# shield.net
KiCad netlist of a schematic drawn in EAGLE
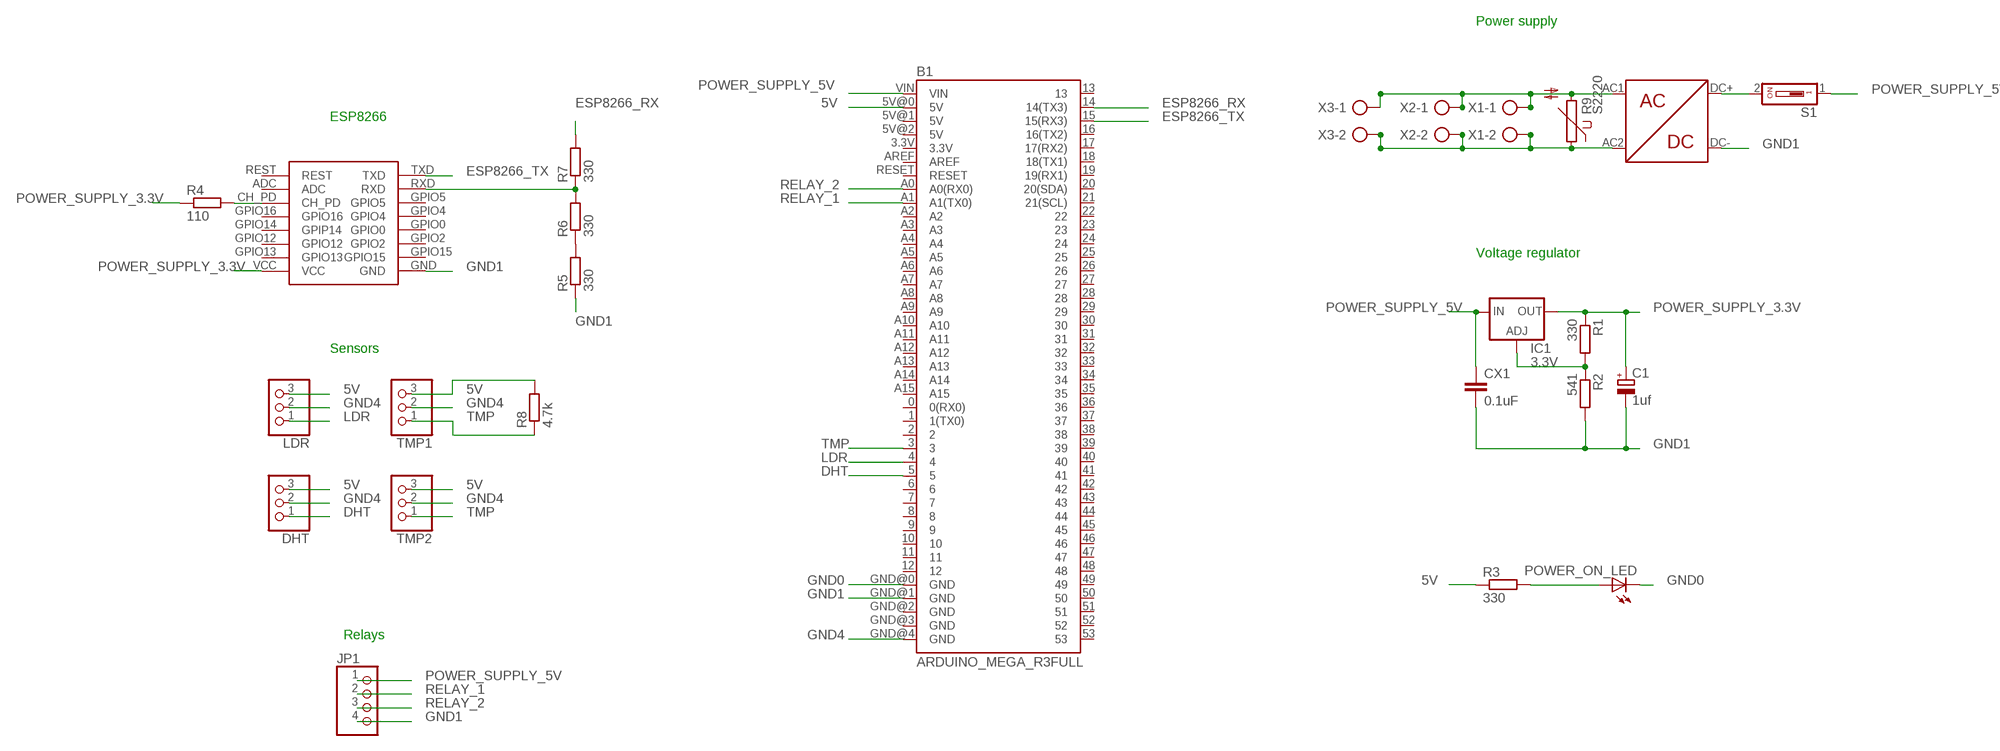
[diagram p0: schematic, sheet 1]

(export (version "E")
  (design (tool "Eeschema 10.0.6"))
  (components
    (comp (ref "B1")
      (value "ARDUINO_MEGA_R3FULL")
      (footprint "eagle-import:ARDUINO_MEGA")
      (libsource (lib "eagle-import") (part "ARDUINO_MEGA_R3FULL"))
    )
    (comp (ref "C1")
      (value "1uf")
      (footprint "eagle-import:TT2D5")
      (libsource (lib "eagle-import") (part "CPOL-EUTT2D5"))
    )
    (comp (ref "CX1")
      (value "0.1uF")
      (footprint "eagle-import:XC10B5")
      (libsource (lib "eagle-import") (part "CXXC10B5"))
    )
    (comp (ref "DHT")
      (value "PINHD-1X3")
      (footprint "eagle-import:1X03")
      (libsource (lib "eagle-import") (part "PINHD-1X3"))
    )
    (comp (ref "IC1")
      (value "3.3V")
      (footprint "eagle-import:317TL")
      (libsource (lib "eagle-import") (part "LM317TL"))
    )
    (comp (ref "JP1")
      (value "PINHD-1X4")
      (footprint "eagle-import:1X04")
      (libsource (lib "eagle-import") (part "PINHD-1X4"))
    )
    (comp (ref "LDR")
      (value "PINHD-1X3")
      (footprint "eagle-import:1X03")
      (libsource (lib "eagle-import") (part "PINHD-1X3"))
    )
    (comp (ref "POWER_ON_LED")
      (value "LED5MM")
      (footprint "eagle-import:LED5MM")
      (libsource (lib "eagle-import") (part "LED5MM"))
    )
    (comp (ref "R1")
      (value "330")
      (footprint "eagle-import:0204_7")
      (libsource (lib "eagle-import") (part "R0204/7"))
    )
    (comp (ref "R2")
      (value "541")
      (footprint "eagle-import:0204_7")
      (libsource (lib "eagle-import") (part "R0204/7"))
    )
    (comp (ref "R3")
      (value "330")
      (footprint "eagle-import:0204_7")
      (libsource (lib "eagle-import") (part "R0204/7"))
    )
    (comp (ref "R4")
      (value "110")
      (footprint "eagle-import:0204_7")
      (libsource (lib "eagle-import") (part "R0204/7"))
    )
    (comp (ref "R5")
      (value "330")
      (footprint "eagle-import:0204_7")
      (libsource (lib "eagle-import") (part "R0204/7"))
    )
    (comp (ref "R6")
      (value "330")
      (footprint "eagle-import:0204_7")
      (libsource (lib "eagle-import") (part "R0204/7"))
    )
    (comp (ref "R7")
      (value "330")
      (footprint "eagle-import:0204_7")
      (libsource (lib "eagle-import") (part "R0204/7"))
    )
    (comp (ref "R8")
      (value "4.7k")
      (footprint "eagle-import:0204_7")
      (libsource (lib "eagle-import") (part "R0204/7"))
    )
    (comp (ref "R9")
      (value "S2220")
      (footprint "eagle-import:S2220")
      (libsource (lib "eagle-import") (part "S2220"))
    )
    (comp (ref "S1")
      (value "SD4-01")
      (footprint "eagle-import:SD4-01")
      (libsource (lib "eagle-import") (part "SD4-01"))
    )
    (comp (ref "TMP1")
      (value "PINHD-1X3")
      (footprint "eagle-import:1X03")
      (libsource (lib "eagle-import") (part "PINHD-1X3"))
    )
    (comp (ref "TMP2")
      (value "PINHD-1X3")
      (footprint "eagle-import:1X03")
      (libsource (lib "eagle-import") (part "PINHD-1X3"))
    )
    (comp (ref "U$1")
      (value "HLK-PM01")
      (footprint "eagle-import:HLK-PM01")
      (libsource (lib "eagle-import") (part "HLK-PM01"))
    )
    (comp (ref "U$4")
      (value "ESP8266_SHIELD")
      (footprint "eagle-import:ESP8266_SHIELD")
      (libsource (lib "eagle-import") (part "ESP8266_SHIELD"))
    )
    (comp (ref "X1")
      (value "AK500/2-H")
      (footprint "eagle-import:AK500_2-H")
      (libsource (lib "eagle-import") (part "AK500/2-H"))
    )
    (comp (ref "X2")
      (value "AK500/2-H")
      (footprint "eagle-import:AK500_2-H")
      (libsource (lib "eagle-import") (part "AK500/2-H"))
    )
    (comp (ref "X3")
      (value "AK500/2-H")
      (footprint "eagle-import:AK500_2-H")
      (libsource (lib "eagle-import") (part "AK500/2-H"))
    )
  )
  (nets
    (net (code "1") (name "/5V") (class "Default")
      (node (ref "B1") (pin "5V@0") (pinfunction "5V_5V@0") (pintype "bidirectional"))
      (node (ref "DHT") (pin "3") (pinfunction "3_3") (pintype "passive"))
      (node (ref "LDR") (pin "3") (pinfunction "3_3") (pintype "passive"))
      (node (ref "R3") (pin "1") (pinfunction "1_1") (pintype "passive"))
      (node (ref "R8") (pin "2") (pinfunction "2_2") (pintype "passive"))
      (node (ref "TMP1") (pin "3") (pinfunction "3_3") (pintype "passive"))
      (node (ref "TMP2") (pin "3") (pinfunction "3_3") (pintype "passive"))
    )
    (net (code "2") (name "/DHT") (class "Default")
      (node (ref "B1") (pin "5") (pinfunction "5_5") (pintype "bidirectional"))
      (node (ref "DHT") (pin "1") (pinfunction "1_1") (pintype "passive"))
    )
    (net (code "3") (name "/ESP8266_RX") (class "Default")
      (node (ref "B1") (pin "14") (pinfunction "14(TX3)_14") (pintype "bidirectional"))
      (node (ref "R7") (pin "2") (pinfunction "2_2") (pintype "passive"))
    )
    (net (code "4") (name "/ESP8266_TX") (class "Default")
      (node (ref "B1") (pin "15") (pinfunction "15(RX3)_15") (pintype "bidirectional"))
      (node (ref "U$4") (pin "TXD") (pinfunction "TXD_TXD") (pintype "bidirectional"))
    )
    (net (code "5") (name "/GND0") (class "Default")
      (node (ref "B1") (pin "GND@0") (pinfunction "GND_GND@0") (pintype "bidirectional"))
      (node (ref "POWER_ON_LED") (pin "K") (pinfunction "C_K") (pintype "passive"))
    )
    (net (code "6") (name "/GND1") (class "Default")
      (node (ref "B1") (pin "GND@1") (pinfunction "GND_GND@1") (pintype "bidirectional"))
      (node (ref "C1") (pin "-") (pinfunction "-_-") (pintype "passive"))
      (node (ref "CX1") (pin "2") (pinfunction "2_2") (pintype "passive"))
      (node (ref "JP1") (pin "4") (pinfunction "4_4") (pintype "passive"))
      (node (ref "R2") (pin "2") (pinfunction "2_2") (pintype "passive"))
      (node (ref "R5") (pin "1") (pinfunction "1_1") (pintype "passive"))
      (node (ref "U$1") (pin "DC-") (pinfunction "DC-_DC-") (pintype "power_in"))
      (node (ref "U$4") (pin "GND") (pinfunction "GND_GND") (pintype "bidirectional"))
    )
    (net (code "7") (name "/GND4") (class "Default")
      (node (ref "B1") (pin "GND@4") (pinfunction "GND_GND@4") (pintype "bidirectional"))
      (node (ref "DHT") (pin "2") (pinfunction "2_2") (pintype "passive"))
      (node (ref "LDR") (pin "2") (pinfunction "2_2") (pintype "passive"))
      (node (ref "TMP1") (pin "2") (pinfunction "2_2") (pintype "passive"))
      (node (ref "TMP2") (pin "2") (pinfunction "2_2") (pintype "passive"))
    )
    (net (code "8") (name "/LDR") (class "Default")
      (node (ref "B1") (pin "4") (pinfunction "4_4") (pintype "bidirectional"))
      (node (ref "LDR") (pin "1") (pinfunction "1_1") (pintype "passive"))
    )
    (net (code "9") (name "/POWER_SUPPLY_3.3V") (class "Default")
      (node (ref "C1") (pin "+") (pinfunction "+_+") (pintype "passive"))
      (node (ref "IC1") (pin "2") (pinfunction "OUT_2") (pintype "passive"))
      (node (ref "R1") (pin "1") (pinfunction "1_1") (pintype "passive"))
      (node (ref "R4") (pin "1") (pinfunction "1_1") (pintype "passive"))
      (node (ref "U$4") (pin "VCC") (pinfunction "VCC_VCC") (pintype "bidirectional"))
    )
    (net (code "10") (name "/POWER_SUPPLY_5V") (class "Default")
      (node (ref "B1") (pin "VIN") (pinfunction "VIN_VIN") (pintype "bidirectional"))
      (node (ref "CX1") (pin "1") (pinfunction "1_1") (pintype "passive"))
      (node (ref "IC1") (pin "3") (pinfunction "IN_3") (pintype "input"))
      (node (ref "JP1") (pin "1") (pinfunction "1_1") (pintype "passive"))
      (node (ref "S1") (pin "1") (pinfunction "1_1") (pintype "passive"))
    )
    (net (code "11") (name "/RELAY_1") (class "Default")
      (node (ref "B1") (pin "A1") (pinfunction "A1(TX0)_A1") (pintype "bidirectional"))
      (node (ref "JP1") (pin "2") (pinfunction "2_2") (pintype "passive"))
    )
    (net (code "12") (name "/RELAY_2") (class "Default")
      (node (ref "B1") (pin "A0") (pinfunction "A0(RX0)_A0") (pintype "bidirectional"))
      (node (ref "JP1") (pin "3") (pinfunction "3_3") (pintype "passive"))
    )
    (net (code "13") (name "/TMP") (class "Default")
      (node (ref "B1") (pin "3") (pinfunction "3_3") (pintype "bidirectional"))
      (node (ref "R8") (pin "1") (pinfunction "1_1") (pintype "passive"))
      (node (ref "TMP1") (pin "1") (pinfunction "1_1") (pintype "passive"))
      (node (ref "TMP2") (pin "1") (pinfunction "1_1") (pintype "passive"))
    )
    (net (code "14") (name "Net-(IC1-ADJ)") (class "Default")
      (node (ref "IC1") (pin "1") (pinfunction "ADJ_1") (pintype "input"))
      (node (ref "R1") (pin "2") (pinfunction "2_2") (pintype "passive"))
      (node (ref "R2") (pin "1") (pinfunction "1_1") (pintype "passive"))
    )
    (net (code "15") (name "Net-(POWER_ON_LED-PadA)") (class "Default")
      (node (ref "POWER_ON_LED") (pin "A") (pinfunction "A_A") (pintype "passive"))
      (node (ref "R3") (pin "2") (pinfunction "2_2") (pintype "passive"))
    )
    (net (code "16") (name "Net-(R4-Pad2)") (class "Default")
      (node (ref "R4") (pin "2") (pinfunction "2_2") (pintype "passive"))
      (node (ref "U$4") (pin "CH_PD") (pinfunction "CH_PD_CH_PD") (pintype "bidirectional"))
    )
    (net (code "17") (name "Net-(R5-Pad2)") (class "Default")
      (node (ref "R5") (pin "2") (pinfunction "2_2") (pintype "passive"))
      (node (ref "R6") (pin "1") (pinfunction "1_1") (pintype "passive"))
    )
    (net (code "18") (name "Net-(R6-Pad2)") (class "Default")
      (node (ref "R6") (pin "2") (pinfunction "2_2") (pintype "passive"))
      (node (ref "R7") (pin "1") (pinfunction "1_1") (pintype "passive"))
      (node (ref "U$4") (pin "RXD") (pinfunction "RXD_RXD") (pintype "bidirectional"))
    )
    (net (code "19") (name "Net-(S1-Pad2)") (class "Default")
      (node (ref "S1") (pin "2") (pinfunction "2_2") (pintype "passive"))
      (node (ref "U$1") (pin "DC+") (pinfunction "DC+_DC+") (pintype "power_in"))
    )
    (net (code "20") (name "Net-(X1A-KL)") (class "Default")
      (node (ref "R9") (pin "2") (pinfunction "2_2") (pintype "passive"))
      (node (ref "U$1") (pin "AC1") (pinfunction "AC1_AC1") (pintype "power_in"))
      (node (ref "X1") (pin "1") (pinfunction "KL_1") (pintype "passive"))
      (node (ref "X2") (pin "1") (pinfunction "KL_1") (pintype "passive"))
      (node (ref "X3") (pin "1") (pinfunction "KL_1") (pintype "passive"))
    )
    (net (code "21") (name "Net-(X1B-KL)") (class "Default")
      (node (ref "R9") (pin "1") (pinfunction "1_1") (pintype "passive"))
      (node (ref "U$1") (pin "AC2") (pinfunction "AC2_AC2") (pintype "power_in"))
      (node (ref "X1") (pin "2") (pinfunction "KL_2") (pintype "passive"))
      (node (ref "X2") (pin "2") (pinfunction "KL_2") (pintype "passive"))
      (node (ref "X3") (pin "2") (pinfunction "KL_2") (pintype "passive"))
    )
    (net (code "22") (name "unconnected-(B1-0(RX0)-Pad0)") (class "Default")
      (node (ref "B1") (pin "0") (pinfunction "0(RX0)_0") (pintype "bidirectional"))
    )
    (net (code "23") (name "unconnected-(B1-1(TX0)-Pad1)") (class "Default")
      (node (ref "B1") (pin "1") (pinfunction "1(TX0)_1") (pintype "bidirectional"))
    )
    (net (code "24") (name "unconnected-(B1-5V-Pad5V@1)") (class "Default")
      (node (ref "B1") (pin "5V@1") (pinfunction "5V_5V@1") (pintype "bidirectional"))
    )
    (net (code "25") (name "unconnected-(B1-5V-Pad5V@2)") (class "Default")
      (node (ref "B1") (pin "5V@2") (pinfunction "5V_5V@2") (pintype "bidirectional"))
    )
    (net (code "26") (name "unconnected-(B1-16(TX2)-Pad16)") (class "Default")
      (node (ref "B1") (pin "16") (pinfunction "16(TX2)_16") (pintype "bidirectional"))
    )
    (net (code "27") (name "unconnected-(B1-17(RX2)-Pad17)") (class "Default")
      (node (ref "B1") (pin "17") (pinfunction "17(RX2)_17") (pintype "bidirectional"))
    )
    (net (code "28") (name "unconnected-(B1-18(TX1)-Pad18)") (class "Default")
      (node (ref "B1") (pin "18") (pinfunction "18(TX1)_18") (pintype "bidirectional"))
    )
    (net (code "29") (name "unconnected-(B1-19(RX1)-Pad19)") (class "Default")
      (node (ref "B1") (pin "19") (pinfunction "19(RX1)_19") (pintype "bidirectional"))
    )
    (net (code "30") (name "unconnected-(B1-20(SDA)-Pad20)") (class "Default")
      (node (ref "B1") (pin "20") (pinfunction "20(SDA)_20") (pintype "bidirectional"))
    )
    (net (code "31") (name "unconnected-(B1-21(SCL)-Pad21)") (class "Default")
      (node (ref "B1") (pin "21") (pinfunction "21(SCL)_21") (pintype "bidirectional"))
    )
    (net (code "32") (name "unconnected-(B1-GND-PadGND@2)") (class "Default")
      (node (ref "B1") (pin "GND@2") (pinfunction "GND_GND@2") (pintype "bidirectional"))
    )
    (net (code "33") (name "unconnected-(B1-GND-PadGND@3)") (class "Default")
      (node (ref "B1") (pin "GND@3") (pinfunction "GND_GND@3") (pintype "bidirectional"))
    )
    (net (code "34") (name "unconnected-(B1-Pad2)") (class "Default")
      (node (ref "B1") (pin "2") (pinfunction "2_2") (pintype "bidirectional"))
    )
    (net (code "35") (name "unconnected-(B1-Pad3.3V)") (class "Default")
      (node (ref "B1") (pin "3.3V") (pinfunction "3.3V_3.3V") (pintype "bidirectional"))
    )
    (net (code "36") (name "unconnected-(B1-Pad6)") (class "Default")
      (node (ref "B1") (pin "6") (pinfunction "6_6") (pintype "bidirectional"))
    )
    (net (code "37") (name "unconnected-(B1-Pad7)") (class "Default")
      (node (ref "B1") (pin "7") (pinfunction "7_7") (pintype "bidirectional"))
    )
    (net (code "38") (name "unconnected-(B1-Pad8)") (class "Default")
      (node (ref "B1") (pin "8") (pinfunction "8_8") (pintype "bidirectional"))
    )
    (net (code "39") (name "unconnected-(B1-Pad9)") (class "Default")
      (node (ref "B1") (pin "9") (pinfunction "9_9") (pintype "bidirectional"))
    )
    (net (code "40") (name "unconnected-(B1-Pad10)") (class "Default")
      (node (ref "B1") (pin "10") (pinfunction "10_10") (pintype "bidirectional"))
    )
    (net (code "41") (name "unconnected-(B1-Pad11)") (class "Default")
      (node (ref "B1") (pin "11") (pinfunction "11_11") (pintype "bidirectional"))
    )
    (net (code "42") (name "unconnected-(B1-Pad12)") (class "Default")
      (node (ref "B1") (pin "12") (pinfunction "12_12") (pintype "bidirectional"))
    )
    (net (code "43") (name "unconnected-(B1-Pad13)") (class "Default")
      (node (ref "B1") (pin "13") (pinfunction "13_13") (pintype "bidirectional"))
    )
    (net (code "44") (name "unconnected-(B1-Pad22)") (class "Default")
      (node (ref "B1") (pin "22") (pinfunction "22_22") (pintype "bidirectional"))
    )
    (net (code "45") (name "unconnected-(B1-Pad23)") (class "Default")
      (node (ref "B1") (pin "23") (pinfunction "23_23") (pintype "bidirectional"))
    )
    (net (code "46") (name "unconnected-(B1-Pad24)") (class "Default")
      (node (ref "B1") (pin "24") (pinfunction "24_24") (pintype "bidirectional"))
    )
    (net (code "47") (name "unconnected-(B1-Pad25)") (class "Default")
      (node (ref "B1") (pin "25") (pinfunction "25_25") (pintype "bidirectional"))
    )
    (net (code "48") (name "unconnected-(B1-Pad26)") (class "Default")
      (node (ref "B1") (pin "26") (pinfunction "26_26") (pintype "bidirectional"))
    )
    (net (code "49") (name "unconnected-(B1-Pad27)") (class "Default")
      (node (ref "B1") (pin "27") (pinfunction "27_27") (pintype "bidirectional"))
    )
    (net (code "50") (name "unconnected-(B1-Pad28)") (class "Default")
      (node (ref "B1") (pin "28") (pinfunction "28_28") (pintype "bidirectional"))
    )
    (net (code "51") (name "unconnected-(B1-Pad29)") (class "Default")
      (node (ref "B1") (pin "29") (pinfunction "29_29") (pintype "bidirectional"))
    )
    (net (code "52") (name "unconnected-(B1-Pad30)") (class "Default")
      (node (ref "B1") (pin "30") (pinfunction "30_30") (pintype "bidirectional"))
    )
    (net (code "53") (name "unconnected-(B1-Pad31)") (class "Default")
      (node (ref "B1") (pin "31") (pinfunction "31_31") (pintype "bidirectional"))
    )
    (net (code "54") (name "unconnected-(B1-Pad32)") (class "Default")
      (node (ref "B1") (pin "32") (pinfunction "32_32") (pintype "bidirectional"))
    )
    (net (code "55") (name "unconnected-(B1-Pad33)") (class "Default")
      (node (ref "B1") (pin "33") (pinfunction "33_33") (pintype "bidirectional"))
    )
    (net (code "56") (name "unconnected-(B1-Pad34)") (class "Default")
      (node (ref "B1") (pin "34") (pinfunction "34_34") (pintype "bidirectional"))
    )
    (net (code "57") (name "unconnected-(B1-Pad35)") (class "Default")
      (node (ref "B1") (pin "35") (pinfunction "35_35") (pintype "bidirectional"))
    )
    (net (code "58") (name "unconnected-(B1-Pad36)") (class "Default")
      (node (ref "B1") (pin "36") (pinfunction "36_36") (pintype "bidirectional"))
    )
    (net (code "59") (name "unconnected-(B1-Pad37)") (class "Default")
      (node (ref "B1") (pin "37") (pinfunction "37_37") (pintype "bidirectional"))
    )
    (net (code "60") (name "unconnected-(B1-Pad38)") (class "Default")
      (node (ref "B1") (pin "38") (pinfunction "38_38") (pintype "bidirectional"))
    )
    (net (code "61") (name "unconnected-(B1-Pad39)") (class "Default")
      (node (ref "B1") (pin "39") (pinfunction "39_39") (pintype "bidirectional"))
    )
    (net (code "62") (name "unconnected-(B1-Pad40)") (class "Default")
      (node (ref "B1") (pin "40") (pinfunction "40_40") (pintype "bidirectional"))
    )
    (net (code "63") (name "unconnected-(B1-Pad41)") (class "Default")
      (node (ref "B1") (pin "41") (pinfunction "41_41") (pintype "bidirectional"))
    )
    (net (code "64") (name "unconnected-(B1-Pad42)") (class "Default")
      (node (ref "B1") (pin "42") (pinfunction "42_42") (pintype "bidirectional"))
    )
    (net (code "65") (name "unconnected-(B1-Pad43)") (class "Default")
      (node (ref "B1") (pin "43") (pinfunction "43_43") (pintype "bidirectional"))
    )
    (net (code "66") (name "unconnected-(B1-Pad44)") (class "Default")
      (node (ref "B1") (pin "44") (pinfunction "44_44") (pintype "bidirectional"))
    )
    (net (code "67") (name "unconnected-(B1-Pad45)") (class "Default")
      (node (ref "B1") (pin "45") (pinfunction "45_45") (pintype "bidirectional"))
    )
    (net (code "68") (name "unconnected-(B1-Pad46)") (class "Default")
      (node (ref "B1") (pin "46") (pinfunction "46_46") (pintype "bidirectional"))
    )
    (net (code "69") (name "unconnected-(B1-Pad47)") (class "Default")
      (node (ref "B1") (pin "47") (pinfunction "47_47") (pintype "bidirectional"))
    )
    (net (code "70") (name "unconnected-(B1-Pad48)") (class "Default")
      (node (ref "B1") (pin "48") (pinfunction "48_48") (pintype "bidirectional"))
    )
    (net (code "71") (name "unconnected-(B1-Pad49)") (class "Default")
      (node (ref "B1") (pin "49") (pinfunction "49_49") (pintype "bidirectional"))
    )
    (net (code "72") (name "unconnected-(B1-Pad50)") (class "Default")
      (node (ref "B1") (pin "50") (pinfunction "50_50") (pintype "bidirectional"))
    )
    (net (code "73") (name "unconnected-(B1-Pad51)") (class "Default")
      (node (ref "B1") (pin "51") (pinfunction "51_51") (pintype "bidirectional"))
    )
    (net (code "74") (name "unconnected-(B1-Pad52)") (class "Default")
      (node (ref "B1") (pin "52") (pinfunction "52_52") (pintype "bidirectional"))
    )
    (net (code "75") (name "unconnected-(B1-Pad53)") (class "Default")
      (node (ref "B1") (pin "53") (pinfunction "53_53") (pintype "bidirectional"))
    )
    (net (code "76") (name "unconnected-(B1-PadA2)") (class "Default")
      (node (ref "B1") (pin "A2") (pinfunction "A2_A2") (pintype "bidirectional"))
    )
    (net (code "77") (name "unconnected-(B1-PadA3)") (class "Default")
      (node (ref "B1") (pin "A3") (pinfunction "A3_A3") (pintype "bidirectional"))
    )
    (net (code "78") (name "unconnected-(B1-PadA4)") (class "Default")
      (node (ref "B1") (pin "A4") (pinfunction "A4_A4") (pintype "bidirectional"))
    )
    (net (code "79") (name "unconnected-(B1-PadA5)") (class "Default")
      (node (ref "B1") (pin "A5") (pinfunction "A5_A5") (pintype "bidirectional"))
    )
    (net (code "80") (name "unconnected-(B1-PadA6)") (class "Default")
      (node (ref "B1") (pin "A6") (pinfunction "A6_A6") (pintype "bidirectional"))
    )
    (net (code "81") (name "unconnected-(B1-PadA7)") (class "Default")
      (node (ref "B1") (pin "A7") (pinfunction "A7_A7") (pintype "bidirectional"))
    )
    (net (code "82") (name "unconnected-(B1-PadA8)") (class "Default")
      (node (ref "B1") (pin "A8") (pinfunction "A8_A8") (pintype "bidirectional"))
    )
    (net (code "83") (name "unconnected-(B1-PadA9)") (class "Default")
      (node (ref "B1") (pin "A9") (pinfunction "A9_A9") (pintype "bidirectional"))
    )
    (net (code "84") (name "unconnected-(B1-PadA10)") (class "Default")
      (node (ref "B1") (pin "A10") (pinfunction "A10_A10") (pintype "bidirectional"))
    )
    (net (code "85") (name "unconnected-(B1-PadA11)") (class "Default")
      (node (ref "B1") (pin "A11") (pinfunction "A11_A11") (pintype "bidirectional"))
    )
    (net (code "86") (name "unconnected-(B1-PadA12)") (class "Default")
      (node (ref "B1") (pin "A12") (pinfunction "A12_A12") (pintype "bidirectional"))
    )
    (net (code "87") (name "unconnected-(B1-PadA13)") (class "Default")
      (node (ref "B1") (pin "A13") (pinfunction "A13_A13") (pintype "bidirectional"))
    )
    (net (code "88") (name "unconnected-(B1-PadA14)") (class "Default")
      (node (ref "B1") (pin "A14") (pinfunction "A14_A14") (pintype "bidirectional"))
    )
    (net (code "89") (name "unconnected-(B1-PadA15)") (class "Default")
      (node (ref "B1") (pin "A15") (pinfunction "A15_A15") (pintype "bidirectional"))
    )
    (net (code "90") (name "unconnected-(B1-PadAREF)") (class "Default")
      (node (ref "B1") (pin "AREF") (pinfunction "AREF_AREF") (pintype "bidirectional"))
    )
    (net (code "91") (name "unconnected-(B1-PadRESET)") (class "Default")
      (node (ref "B1") (pin "RESET") (pinfunction "RESET_RESET") (pintype "bidirectional"))
    )
    (net (code "92") (name "unconnected-(U$4-GPIP14-PadGPIO14)") (class "Default")
      (node (ref "U$4") (pin "GPIO14") (pinfunction "GPIP14_GPIO14") (pintype "bidirectional"))
    )
    (net (code "93") (name "unconnected-(U$4-PadADC)") (class "Default")
      (node (ref "U$4") (pin "ADC") (pinfunction "ADC_ADC") (pintype "bidirectional"))
    )
    (net (code "94") (name "unconnected-(U$4-PadGPIO0)") (class "Default")
      (node (ref "U$4") (pin "GPIO0") (pinfunction "GPIO0_GPIO0") (pintype "bidirectional"))
    )
    (net (code "95") (name "unconnected-(U$4-PadGPIO2)") (class "Default")
      (node (ref "U$4") (pin "GPIO2") (pinfunction "GPIO2_GPIO2") (pintype "bidirectional"))
    )
    (net (code "96") (name "unconnected-(U$4-PadGPIO4)") (class "Default")
      (node (ref "U$4") (pin "GPIO4") (pinfunction "GPIO4_GPIO4") (pintype "bidirectional"))
    )
    (net (code "97") (name "unconnected-(U$4-PadGPIO5)") (class "Default")
      (node (ref "U$4") (pin "GPIO5") (pinfunction "GPIO5_GPIO5") (pintype "bidirectional"))
    )
    (net (code "98") (name "unconnected-(U$4-PadGPIO12)") (class "Default")
      (node (ref "U$4") (pin "GPIO12") (pinfunction "GPIO12_GPIO12") (pintype "bidirectional"))
    )
    (net (code "99") (name "unconnected-(U$4-PadGPIO13)") (class "Default")
      (node (ref "U$4") (pin "GPIO13") (pinfunction "GPIO13_GPIO13") (pintype "bidirectional"))
    )
    (net (code "100") (name "unconnected-(U$4-PadGPIO15)") (class "Default")
      (node (ref "U$4") (pin "GPIO15") (pinfunction "GPIO15_GPIO15") (pintype "bidirectional"))
    )
    (net (code "101") (name "unconnected-(U$4-PadGPIO16)") (class "Default")
      (node (ref "U$4") (pin "GPIO16") (pinfunction "GPIO16_GPIO16") (pintype "bidirectional"))
    )
    (net (code "102") (name "unconnected-(U$4-PadREST)") (class "Default")
      (node (ref "U$4") (pin "REST") (pinfunction "REST_REST") (pintype "bidirectional"))
    )
  )
)
